# esp8266.net
KiCad netlist of a schematic drawn in EAGLE
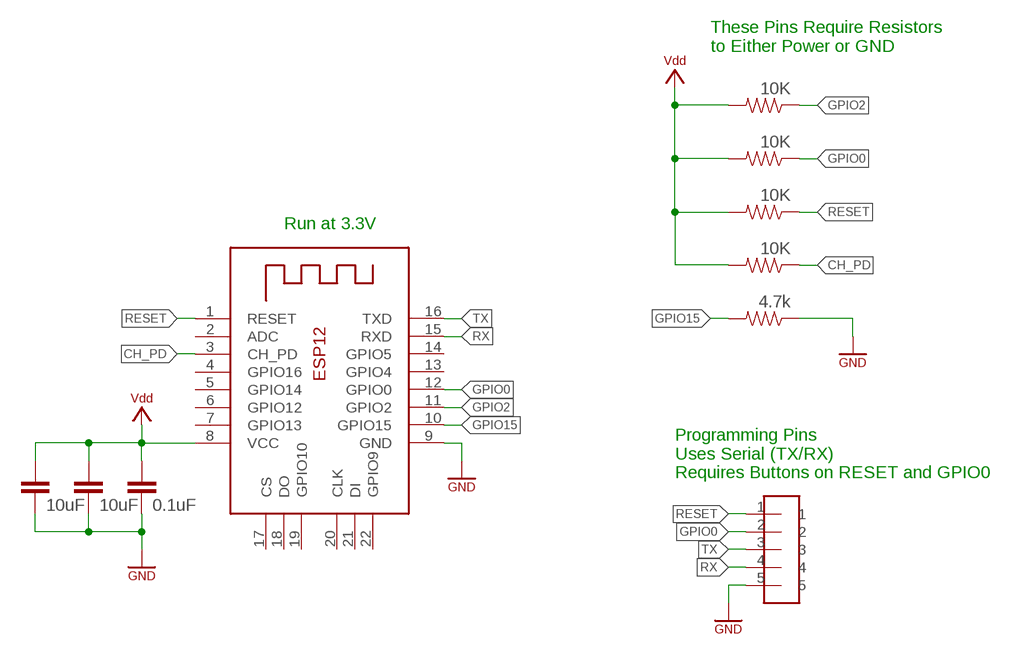
[diagram p0: schematic, sheet 1]

(export (version "E")
  (design (tool "Eeschema 10.0.6"))
  (components
    (comp (ref "C1")
      (value "0.1uF")
      (footprint "eagle-import:0805")
      (libsource (lib "eagle-import") (part "COMPONENT_CAP-0805"))
    )
    (comp (ref "C2")
      (value "10uF")
      (footprint "eagle-import:0805")
      (libsource (lib "eagle-import") (part "COMPONENT_CAP-0805"))
    )
    (comp (ref "C3")
      (value "10uF")
      (footprint "eagle-import:0805")
      (libsource (lib "eagle-import") (part "COMPONENT_CAP-0805"))
    )
    (comp (ref "R1")
      (value "10K")
      (footprint "eagle-import:0805")
      (libsource (lib "eagle-import") (part "COMPONENT_RESISTOR-0805"))
    )
    (comp (ref "R2")
      (value "10K")
      (footprint "eagle-import:0805")
      (libsource (lib "eagle-import") (part "COMPONENT_RESISTOR-0805"))
    )
    (comp (ref "R3")
      (value "10K")
      (footprint "eagle-import:0805")
      (libsource (lib "eagle-import") (part "COMPONENT_RESISTOR-0805"))
    )
    (comp (ref "R4")
      (value "10K")
      (footprint "eagle-import:0805")
      (libsource (lib "eagle-import") (part "COMPONENT_RESISTOR-0805"))
    )
    (comp (ref "R5")
      (value "4.7k")
      (footprint "eagle-import:0805")
      (libsource (lib "eagle-import") (part "COMPONENT_RESISTOR-0805"))
    )
    (comp (ref "U$1")
      (value "HEADER-5-TESTPOINT")
      (footprint "eagle-import:TESTPOINT-5")
      (libsource (lib "eagle-import") (part "HEADER-5-TESTPOINT"))
    )
    (comp (ref "X1")
      (value "MICRO_ESP8266")
      (footprint "eagle-import:ESP-12E")
      (libsource (lib "eagle-import") (part "MICRO_ESP8266"))
    )
  )
  (nets
    (net (code "1") (name "CH_PD") (class "Default")
      (node (ref "R4") (pin "1") (pinfunction "1_1") (pintype "passive"))
      (node (ref "X1") (pin "3") (pinfunction "CH_PD_3") (pintype "input"))
    )
    (net (code "2") (name "GPIO0") (class "Default")
      (node (ref "R2") (pin "1") (pinfunction "1_1") (pintype "passive"))
      (node (ref "U$1") (pin "2") (pinfunction "2_2") (pintype "bidirectional"))
      (node (ref "X1") (pin "12") (pinfunction "GPIO0_12") (pintype "bidirectional"))
    )
    (net (code "3") (name "GPIO2") (class "Default")
      (node (ref "R1") (pin "1") (pinfunction "1_1") (pintype "passive"))
      (node (ref "X1") (pin "11") (pinfunction "GPIO2_11") (pintype "bidirectional"))
    )
    (net (code "4") (name "GPIO15") (class "Default")
      (node (ref "R5") (pin "2") (pinfunction "2_2") (pintype "passive"))
      (node (ref "X1") (pin "10") (pinfunction "GPIO15_10") (pintype "bidirectional"))
    )
    (net (code "5") (name "RESET") (class "Default")
      (node (ref "R3") (pin "1") (pinfunction "1_1") (pintype "passive"))
      (node (ref "U$1") (pin "1") (pinfunction "1_1") (pintype "bidirectional"))
      (node (ref "X1") (pin "1") (pinfunction "RESET_1") (pintype "input"))
    )
    (net (code "6") (name "RX") (class "Default")
      (node (ref "U$1") (pin "4") (pinfunction "4_4") (pintype "bidirectional"))
      (node (ref "X1") (pin "15") (pinfunction "RXD_15") (pintype "input"))
    )
    (net (code "7") (name "SYMBOL_GND") (class "Default")
      (node (ref "C1") (pin "2") (pinfunction "2_2") (pintype "passive"))
      (node (ref "C2") (pin "2") (pinfunction "2_2") (pintype "passive"))
      (node (ref "C3") (pin "2") (pinfunction "2_2") (pintype "passive"))
      (node (ref "R5") (pin "1") (pinfunction "1_1") (pintype "passive"))
      (node (ref "U$1") (pin "5") (pinfunction "5_5") (pintype "bidirectional"))
      (node (ref "X1") (pin "9") (pinfunction "GND_9") (pintype "power_in"))
    )
    (net (code "8") (name "SYMBOL_VDD") (class "Default")
      (node (ref "C1") (pin "1") (pinfunction "1_1") (pintype "passive"))
      (node (ref "C2") (pin "1") (pinfunction "1_1") (pintype "passive"))
      (node (ref "C3") (pin "1") (pinfunction "1_1") (pintype "passive"))
      (node (ref "R1") (pin "2") (pinfunction "2_2") (pintype "passive"))
      (node (ref "R2") (pin "2") (pinfunction "2_2") (pintype "passive"))
      (node (ref "R3") (pin "2") (pinfunction "2_2") (pintype "passive"))
      (node (ref "R4") (pin "2") (pinfunction "2_2") (pintype "passive"))
      (node (ref "X1") (pin "8") (pinfunction "VCC_8") (pintype "power_in"))
    )
    (net (code "9") (name "TX") (class "Default")
      (node (ref "U$1") (pin "3") (pinfunction "3_3") (pintype "bidirectional"))
      (node (ref "X1") (pin "16") (pinfunction "TXD_16") (pintype "output"))
    )
    (net (code "10") (name "unconnected-(X1-ADC-Pad2)") (class "Default")
      (node (ref "X1") (pin "2") (pinfunction "ADC_2") (pintype "passive"))
    )
    (net (code "11") (name "unconnected-(X1-CLK-Pad20)") (class "Default")
      (node (ref "X1") (pin "20") (pinfunction "CLK_20") (pintype "bidirectional"))
    )
    (net (code "12") (name "unconnected-(X1-CS-Pad17)") (class "Default")
      (node (ref "X1") (pin "17") (pinfunction "CS_17") (pintype "bidirectional"))
    )
    (net (code "13") (name "unconnected-(X1-DI-Pad21)") (class "Default")
      (node (ref "X1") (pin "21") (pinfunction "DI_21") (pintype "bidirectional"))
    )
    (net (code "14") (name "unconnected-(X1-DO-Pad18)") (class "Default")
      (node (ref "X1") (pin "18") (pinfunction "DO_18") (pintype "bidirectional"))
    )
    (net (code "15") (name "unconnected-(X1-GPIO4-Pad13)") (class "Default")
      (node (ref "X1") (pin "13") (pinfunction "GPIO4_13") (pintype "bidirectional"))
    )
    (net (code "16") (name "unconnected-(X1-GPIO5-Pad14)") (class "Default")
      (node (ref "X1") (pin "14") (pinfunction "GPIO5_14") (pintype "bidirectional"))
    )
    (net (code "17") (name "unconnected-(X1-GPIO9-Pad22)") (class "Default")
      (node (ref "X1") (pin "22") (pinfunction "GPIO9_22") (pintype "bidirectional"))
    )
    (net (code "18") (name "unconnected-(X1-GPIO10-Pad19)") (class "Default")
      (node (ref "X1") (pin "19") (pinfunction "GPIO10_19") (pintype "bidirectional"))
    )
    (net (code "19") (name "unconnected-(X1-GPIO12-Pad6)") (class "Default")
      (node (ref "X1") (pin "6") (pinfunction "GPIO12_6") (pintype "bidirectional"))
    )
    (net (code "20") (name "unconnected-(X1-GPIO13-Pad7)") (class "Default")
      (node (ref "X1") (pin "7") (pinfunction "GPIO13_7") (pintype "bidirectional"))
    )
    (net (code "21") (name "unconnected-(X1-GPIO14-Pad5)") (class "Default")
      (node (ref "X1") (pin "5") (pinfunction "GPIO14_5") (pintype "bidirectional"))
    )
    (net (code "22") (name "unconnected-(X1-GPIO16-Pad4)") (class "Default")
      (node (ref "X1") (pin "4") (pinfunction "GPIO16_4") (pintype "bidirectional"))
    )
  )
)
